# counter.net
KiCad netlist of a schematic drawn in EAGLE
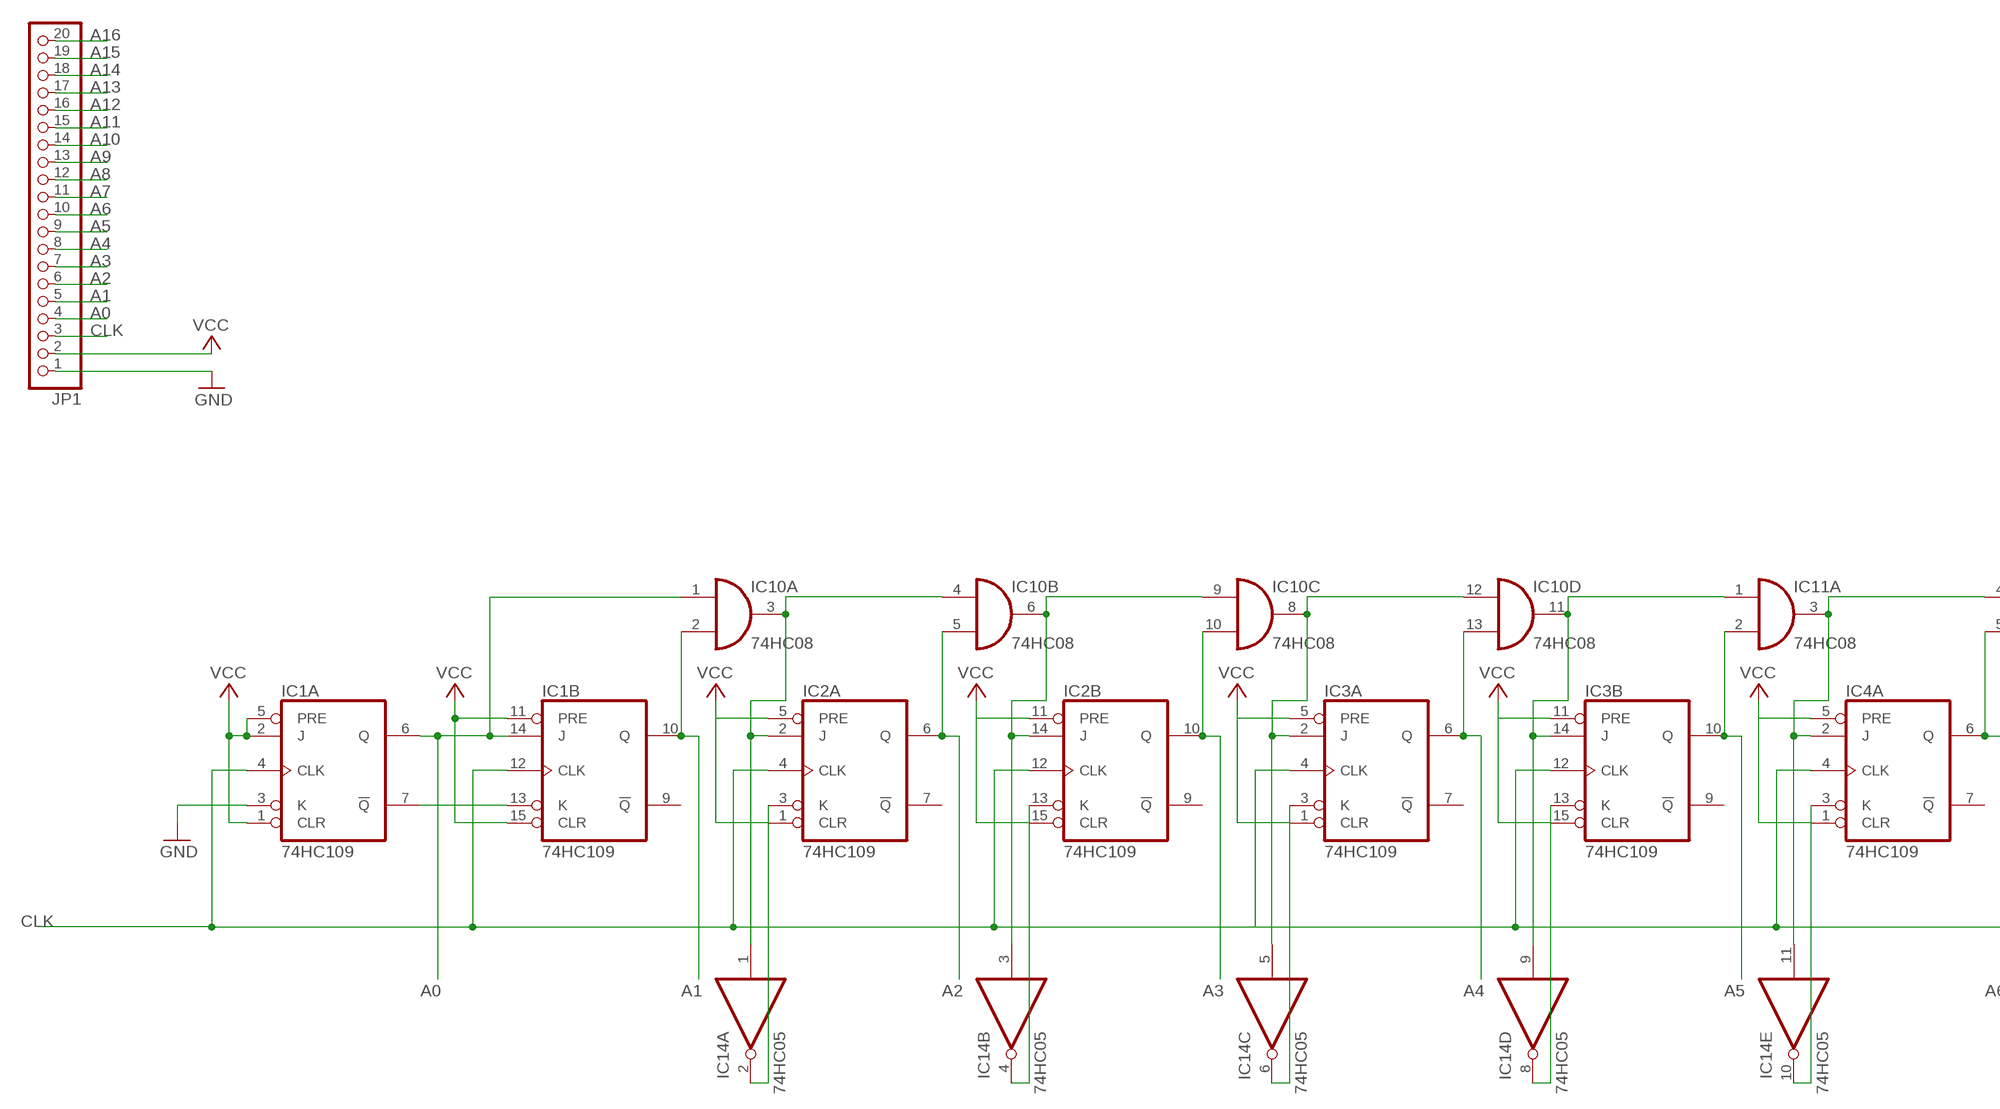
[diagram p0: schematic, sheet 1, part 1 of 2]
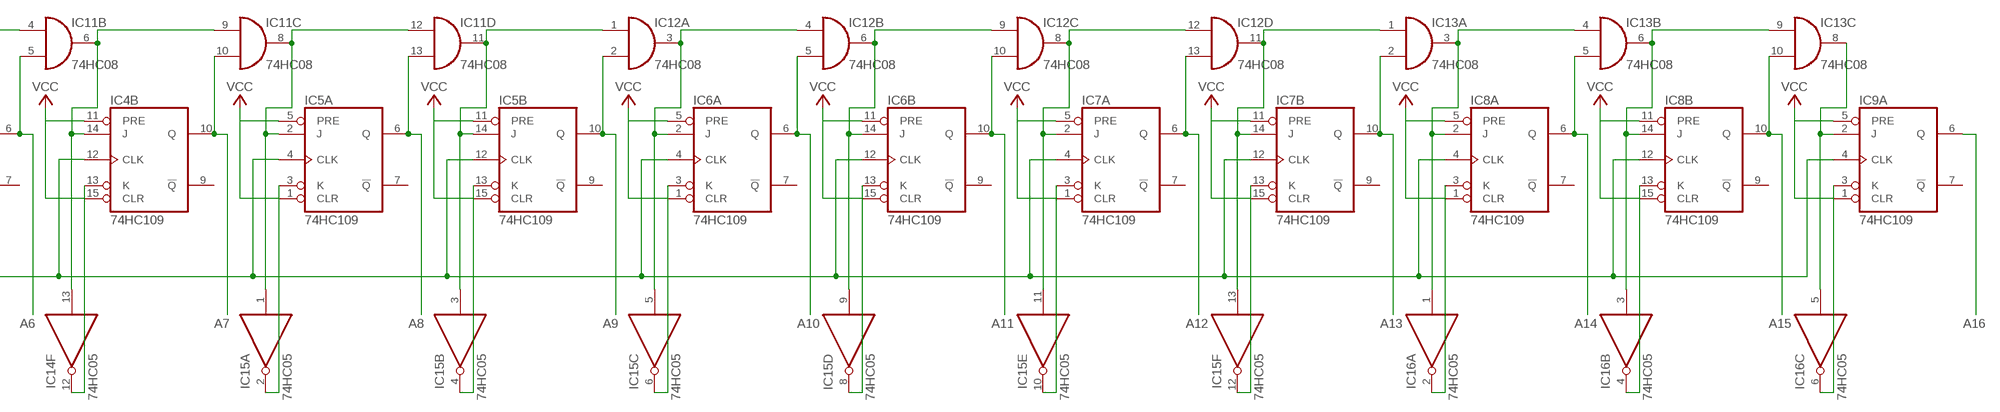
[diagram p1: schematic, sheet 1, part 2 of 2]

(export (version "E")
  (design (tool "Eeschema 10.0.6"))
  (components
    (comp (ref "IC1")
      (value "74HC109")
      (footprint "eagle-import:DIL16")
      (libsource (lib "eagle-import") (part "74109NHC"))
    )
    (comp (ref "IC2")
      (value "74HC109")
      (footprint "eagle-import:DIL16")
      (libsource (lib "eagle-import") (part "74109NHC"))
    )
    (comp (ref "IC3")
      (value "74HC109")
      (footprint "eagle-import:DIL16")
      (libsource (lib "eagle-import") (part "74109NHC"))
    )
    (comp (ref "IC4")
      (value "74HC109")
      (footprint "eagle-import:DIL16")
      (libsource (lib "eagle-import") (part "74109NHC"))
    )
    (comp (ref "IC5")
      (value "74HC109")
      (footprint "eagle-import:DIL16")
      (libsource (lib "eagle-import") (part "74109NHC"))
    )
    (comp (ref "IC6")
      (value "74HC109")
      (footprint "eagle-import:DIL16")
      (libsource (lib "eagle-import") (part "74109NHC"))
    )
    (comp (ref "IC7")
      (value "74HC109")
      (footprint "eagle-import:DIL16")
      (libsource (lib "eagle-import") (part "74109NHC"))
    )
    (comp (ref "IC8")
      (value "74HC109")
      (footprint "eagle-import:DIL16")
      (libsource (lib "eagle-import") (part "74109NHC"))
    )
    (comp (ref "IC9")
      (value "74HC109")
      (footprint "eagle-import:DIL16")
      (libsource (lib "eagle-import") (part "74109NHC"))
    )
    (comp (ref "IC10")
      (value "74HC08")
      (footprint "eagle-import:DIL14")
      (libsource (lib "eagle-import") (part "7408NAC"))
    )
    (comp (ref "IC11")
      (value "74HC08")
      (footprint "eagle-import:DIL14")
      (libsource (lib "eagle-import") (part "7408NAC"))
    )
    (comp (ref "IC12")
      (value "74HC08")
      (footprint "eagle-import:DIL14")
      (libsource (lib "eagle-import") (part "7408NAC"))
    )
    (comp (ref "IC13")
      (value "74HC08")
      (footprint "eagle-import:DIL14")
      (libsource (lib "eagle-import") (part "7408NAC"))
    )
    (comp (ref "IC14")
      (value "74HC05")
      (footprint "eagle-import:DIL14")
      (libsource (lib "eagle-import") (part "7405NALS"))
    )
    (comp (ref "IC15")
      (value "74HC05")
      (footprint "eagle-import:DIL14")
      (libsource (lib "eagle-import") (part "7405NALS"))
    )
    (comp (ref "IC16")
      (value "74HC05")
      (footprint "eagle-import:DIL14")
      (libsource (lib "eagle-import") (part "7405NALS"))
    )
    (comp (ref "JP1")
      (value "PINHD-1X20")
      (footprint "eagle-import:1X20")
      (libsource (lib "eagle-import") (part "PINHD-1X20"))
    )
  )
  (nets
    (net (code "1") (name "/A0") (class "Default")
      (node (ref "IC1") (pin "14") (pinfunction "J_14") (pintype "input"))
      (node (ref "IC1") (pin "6") (pinfunction "Q_6") (pintype "output"))
      (node (ref "IC10") (pin "1") (pinfunction "I0_1") (pintype "input"))
      (node (ref "JP1") (pin "4") (pinfunction "4_4") (pintype "passive"))
    )
    (net (code "2") (name "/A1") (class "Default")
      (node (ref "IC1") (pin "10") (pinfunction "Q_10") (pintype "output"))
      (node (ref "IC10") (pin "2") (pinfunction "I1_2") (pintype "input"))
      (node (ref "JP1") (pin "5") (pinfunction "5_5") (pintype "passive"))
    )
    (net (code "3") (name "/A2") (class "Default")
      (node (ref "IC10") (pin "5") (pinfunction "I1_5") (pintype "input"))
      (node (ref "IC2") (pin "6") (pinfunction "Q_6") (pintype "output"))
      (node (ref "JP1") (pin "6") (pinfunction "6_6") (pintype "passive"))
    )
    (net (code "4") (name "/A3") (class "Default")
      (node (ref "IC10") (pin "10") (pinfunction "I1_10") (pintype "input"))
      (node (ref "IC2") (pin "10") (pinfunction "Q_10") (pintype "output"))
      (node (ref "JP1") (pin "7") (pinfunction "7_7") (pintype "passive"))
    )
    (net (code "5") (name "/A4") (class "Default")
      (node (ref "IC10") (pin "13") (pinfunction "I1_13") (pintype "input"))
      (node (ref "IC3") (pin "6") (pinfunction "Q_6") (pintype "output"))
      (node (ref "JP1") (pin "8") (pinfunction "8_8") (pintype "passive"))
    )
    (net (code "6") (name "/A5") (class "Default")
      (node (ref "IC11") (pin "2") (pinfunction "I1_2") (pintype "input"))
      (node (ref "IC3") (pin "10") (pinfunction "Q_10") (pintype "output"))
      (node (ref "JP1") (pin "9") (pinfunction "9_9") (pintype "passive"))
    )
    (net (code "7") (name "/A6") (class "Default")
      (node (ref "IC11") (pin "5") (pinfunction "I1_5") (pintype "input"))
      (node (ref "IC4") (pin "6") (pinfunction "Q_6") (pintype "output"))
      (node (ref "JP1") (pin "10") (pinfunction "10_10") (pintype "passive"))
    )
    (net (code "8") (name "/A7") (class "Default")
      (node (ref "IC11") (pin "10") (pinfunction "I1_10") (pintype "input"))
      (node (ref "IC4") (pin "10") (pinfunction "Q_10") (pintype "output"))
      (node (ref "JP1") (pin "11") (pinfunction "11_11") (pintype "passive"))
    )
    (net (code "9") (name "/A8") (class "Default")
      (node (ref "IC11") (pin "13") (pinfunction "I1_13") (pintype "input"))
      (node (ref "IC5") (pin "6") (pinfunction "Q_6") (pintype "output"))
      (node (ref "JP1") (pin "12") (pinfunction "12_12") (pintype "passive"))
    )
    (net (code "10") (name "/A9") (class "Default")
      (node (ref "IC12") (pin "2") (pinfunction "I1_2") (pintype "input"))
      (node (ref "IC5") (pin "10") (pinfunction "Q_10") (pintype "output"))
      (node (ref "JP1") (pin "13") (pinfunction "13_13") (pintype "passive"))
    )
    (net (code "11") (name "/A10") (class "Default")
      (node (ref "IC12") (pin "5") (pinfunction "I1_5") (pintype "input"))
      (node (ref "IC6") (pin "6") (pinfunction "Q_6") (pintype "output"))
      (node (ref "JP1") (pin "14") (pinfunction "14_14") (pintype "passive"))
    )
    (net (code "12") (name "/A11") (class "Default")
      (node (ref "IC12") (pin "10") (pinfunction "I1_10") (pintype "input"))
      (node (ref "IC6") (pin "10") (pinfunction "Q_10") (pintype "output"))
      (node (ref "JP1") (pin "15") (pinfunction "15_15") (pintype "passive"))
    )
    (net (code "13") (name "/A12") (class "Default")
      (node (ref "IC12") (pin "13") (pinfunction "I1_13") (pintype "input"))
      (node (ref "IC7") (pin "6") (pinfunction "Q_6") (pintype "output"))
      (node (ref "JP1") (pin "16") (pinfunction "16_16") (pintype "passive"))
    )
    (net (code "14") (name "/A13") (class "Default")
      (node (ref "IC13") (pin "2") (pinfunction "I1_2") (pintype "input"))
      (node (ref "IC7") (pin "10") (pinfunction "Q_10") (pintype "output"))
      (node (ref "JP1") (pin "17") (pinfunction "17_17") (pintype "passive"))
    )
    (net (code "15") (name "/A14") (class "Default")
      (node (ref "IC13") (pin "5") (pinfunction "I1_5") (pintype "input"))
      (node (ref "IC8") (pin "6") (pinfunction "Q_6") (pintype "output"))
      (node (ref "JP1") (pin "18") (pinfunction "18_18") (pintype "passive"))
    )
    (net (code "16") (name "/A15") (class "Default")
      (node (ref "IC13") (pin "10") (pinfunction "I1_10") (pintype "input"))
      (node (ref "IC8") (pin "10") (pinfunction "Q_10") (pintype "output"))
      (node (ref "JP1") (pin "19") (pinfunction "19_19") (pintype "passive"))
    )
    (net (code "17") (name "/A16") (class "Default")
      (node (ref "IC9") (pin "6") (pinfunction "Q_6") (pintype "output"))
      (node (ref "JP1") (pin "20") (pinfunction "20_20") (pintype "passive"))
    )
    (net (code "18") (name "/CLK") (class "Default")
      (node (ref "IC1") (pin "12") (pinfunction "CLK_12") (pintype "input"))
      (node (ref "IC1") (pin "4") (pinfunction "CLK_4") (pintype "input"))
      (node (ref "IC2") (pin "12") (pinfunction "CLK_12") (pintype "input"))
      (node (ref "IC2") (pin "4") (pinfunction "CLK_4") (pintype "input"))
      (node (ref "IC3") (pin "12") (pinfunction "CLK_12") (pintype "input"))
      (node (ref "IC3") (pin "4") (pinfunction "CLK_4") (pintype "input"))
      (node (ref "IC4") (pin "12") (pinfunction "CLK_12") (pintype "input"))
      (node (ref "IC4") (pin "4") (pinfunction "CLK_4") (pintype "input"))
      (node (ref "IC5") (pin "12") (pinfunction "CLK_12") (pintype "input"))
      (node (ref "IC5") (pin "4") (pinfunction "CLK_4") (pintype "input"))
      (node (ref "IC6") (pin "12") (pinfunction "CLK_12") (pintype "input"))
      (node (ref "IC6") (pin "4") (pinfunction "CLK_4") (pintype "input"))
      (node (ref "IC7") (pin "12") (pinfunction "CLK_12") (pintype "input"))
      (node (ref "IC7") (pin "4") (pinfunction "CLK_4") (pintype "input"))
      (node (ref "IC8") (pin "12") (pinfunction "CLK_12") (pintype "input"))
      (node (ref "IC8") (pin "4") (pinfunction "CLK_4") (pintype "input"))
      (node (ref "IC9") (pin "4") (pinfunction "CLK_4") (pintype "input"))
      (node (ref "JP1") (pin "3") (pinfunction "3_3") (pintype "passive"))
    )
    (net (code "19") (name "GND") (class "Default")
      (node (ref "IC1") (pin "3") (pinfunction "K_3") (pintype "input"))
      (node (ref "JP1") (pin "1") (pinfunction "1_1") (pintype "passive"))
    )
    (net (code "20") (name "Net-(IC1A-~{Q})") (class "Default")
      (node (ref "IC1") (pin "13") (pinfunction "K_13") (pintype "input"))
      (node (ref "IC1") (pin "7") (pinfunction "~{Q}_7") (pintype "output"))
    )
    (net (code "21") (name "Net-(IC10A-O)") (class "Default")
      (node (ref "IC10") (pin "3") (pinfunction "O_3") (pintype "output"))
      (node (ref "IC10") (pin "4") (pinfunction "I0_4") (pintype "input"))
      (node (ref "IC14") (pin "1") (pinfunction "I_1") (pintype "input"))
      (node (ref "IC2") (pin "2") (pinfunction "J_2") (pintype "input"))
    )
    (net (code "22") (name "Net-(IC10B-O)") (class "Default")
      (node (ref "IC10") (pin "6") (pinfunction "O_6") (pintype "output"))
      (node (ref "IC10") (pin "9") (pinfunction "I0_9") (pintype "input"))
      (node (ref "IC14") (pin "3") (pinfunction "I_3") (pintype "input"))
      (node (ref "IC2") (pin "14") (pinfunction "J_14") (pintype "input"))
    )
    (net (code "23") (name "Net-(IC10C-O)") (class "Default")
      (node (ref "IC10") (pin "12") (pinfunction "I0_12") (pintype "input"))
      (node (ref "IC10") (pin "8") (pinfunction "O_8") (pintype "output"))
      (node (ref "IC14") (pin "5") (pinfunction "I_5") (pintype "input"))
      (node (ref "IC3") (pin "2") (pinfunction "J_2") (pintype "input"))
    )
    (net (code "24") (name "Net-(IC10D-O)") (class "Default")
      (node (ref "IC10") (pin "11") (pinfunction "O_11") (pintype "output"))
      (node (ref "IC11") (pin "1") (pinfunction "I0_1") (pintype "input"))
      (node (ref "IC14") (pin "9") (pinfunction "I_9") (pintype "input"))
      (node (ref "IC3") (pin "14") (pinfunction "J_14") (pintype "input"))
    )
    (net (code "25") (name "Net-(IC11A-O)") (class "Default")
      (node (ref "IC11") (pin "3") (pinfunction "O_3") (pintype "output"))
      (node (ref "IC11") (pin "4") (pinfunction "I0_4") (pintype "input"))
      (node (ref "IC14") (pin "11") (pinfunction "I_11") (pintype "input"))
      (node (ref "IC4") (pin "2") (pinfunction "J_2") (pintype "input"))
    )
    (net (code "26") (name "Net-(IC11B-O)") (class "Default")
      (node (ref "IC11") (pin "6") (pinfunction "O_6") (pintype "output"))
      (node (ref "IC11") (pin "9") (pinfunction "I0_9") (pintype "input"))
      (node (ref "IC14") (pin "13") (pinfunction "I_13") (pintype "input"))
      (node (ref "IC4") (pin "14") (pinfunction "J_14") (pintype "input"))
    )
    (net (code "27") (name "Net-(IC11C-O)") (class "Default")
      (node (ref "IC11") (pin "12") (pinfunction "I0_12") (pintype "input"))
      (node (ref "IC11") (pin "8") (pinfunction "O_8") (pintype "output"))
      (node (ref "IC15") (pin "1") (pinfunction "I_1") (pintype "input"))
      (node (ref "IC5") (pin "2") (pinfunction "J_2") (pintype "input"))
    )
    (net (code "28") (name "Net-(IC11D-O)") (class "Default")
      (node (ref "IC11") (pin "11") (pinfunction "O_11") (pintype "output"))
      (node (ref "IC12") (pin "1") (pinfunction "I0_1") (pintype "input"))
      (node (ref "IC15") (pin "3") (pinfunction "I_3") (pintype "input"))
      (node (ref "IC5") (pin "14") (pinfunction "J_14") (pintype "input"))
    )
    (net (code "29") (name "Net-(IC12A-O)") (class "Default")
      (node (ref "IC12") (pin "3") (pinfunction "O_3") (pintype "output"))
      (node (ref "IC12") (pin "4") (pinfunction "I0_4") (pintype "input"))
      (node (ref "IC15") (pin "5") (pinfunction "I_5") (pintype "input"))
      (node (ref "IC6") (pin "2") (pinfunction "J_2") (pintype "input"))
    )
    (net (code "30") (name "Net-(IC12B-O)") (class "Default")
      (node (ref "IC12") (pin "6") (pinfunction "O_6") (pintype "output"))
      (node (ref "IC12") (pin "9") (pinfunction "I0_9") (pintype "input"))
      (node (ref "IC15") (pin "9") (pinfunction "I_9") (pintype "input"))
      (node (ref "IC6") (pin "14") (pinfunction "J_14") (pintype "input"))
    )
    (net (code "31") (name "Net-(IC12C-O)") (class "Default")
      (node (ref "IC12") (pin "12") (pinfunction "I0_12") (pintype "input"))
      (node (ref "IC12") (pin "8") (pinfunction "O_8") (pintype "output"))
      (node (ref "IC15") (pin "11") (pinfunction "I_11") (pintype "input"))
      (node (ref "IC7") (pin "2") (pinfunction "J_2") (pintype "input"))
    )
    (net (code "32") (name "Net-(IC12D-O)") (class "Default")
      (node (ref "IC12") (pin "11") (pinfunction "O_11") (pintype "output"))
      (node (ref "IC13") (pin "1") (pinfunction "I0_1") (pintype "input"))
      (node (ref "IC15") (pin "13") (pinfunction "I_13") (pintype "input"))
      (node (ref "IC7") (pin "14") (pinfunction "J_14") (pintype "input"))
    )
    (net (code "33") (name "Net-(IC13A-O)") (class "Default")
      (node (ref "IC13") (pin "3") (pinfunction "O_3") (pintype "output"))
      (node (ref "IC13") (pin "4") (pinfunction "I0_4") (pintype "input"))
      (node (ref "IC16") (pin "1") (pinfunction "I_1") (pintype "input"))
      (node (ref "IC8") (pin "2") (pinfunction "J_2") (pintype "input"))
    )
    (net (code "34") (name "Net-(IC13B-O)") (class "Default")
      (node (ref "IC13") (pin "6") (pinfunction "O_6") (pintype "output"))
      (node (ref "IC13") (pin "9") (pinfunction "I0_9") (pintype "input"))
      (node (ref "IC16") (pin "3") (pinfunction "I_3") (pintype "input"))
      (node (ref "IC8") (pin "14") (pinfunction "J_14") (pintype "input"))
    )
    (net (code "35") (name "Net-(IC13C-O)") (class "Default")
      (node (ref "IC13") (pin "8") (pinfunction "O_8") (pintype "output"))
      (node (ref "IC16") (pin "5") (pinfunction "I_5") (pintype "input"))
      (node (ref "IC9") (pin "2") (pinfunction "J_2") (pintype "input"))
    )
    (net (code "36") (name "Net-(IC14A-O)") (class "Default")
      (node (ref "IC14") (pin "2") (pinfunction "O_2") (pintype "open_collector"))
      (node (ref "IC2") (pin "3") (pinfunction "K_3") (pintype "input"))
    )
    (net (code "37") (name "Net-(IC14B-O)") (class "Default")
      (node (ref "IC14") (pin "4") (pinfunction "O_4") (pintype "open_collector"))
      (node (ref "IC2") (pin "13") (pinfunction "K_13") (pintype "input"))
    )
    (net (code "38") (name "Net-(IC14C-O)") (class "Default")
      (node (ref "IC14") (pin "6") (pinfunction "O_6") (pintype "open_collector"))
      (node (ref "IC3") (pin "3") (pinfunction "K_3") (pintype "input"))
    )
    (net (code "39") (name "Net-(IC14D-O)") (class "Default")
      (node (ref "IC14") (pin "8") (pinfunction "O_8") (pintype "open_collector"))
      (node (ref "IC3") (pin "13") (pinfunction "K_13") (pintype "input"))
    )
    (net (code "40") (name "Net-(IC14E-O)") (class "Default")
      (node (ref "IC14") (pin "10") (pinfunction "O_10") (pintype "open_collector"))
      (node (ref "IC4") (pin "3") (pinfunction "K_3") (pintype "input"))
    )
    (net (code "41") (name "Net-(IC14F-O)") (class "Default")
      (node (ref "IC14") (pin "12") (pinfunction "O_12") (pintype "open_collector"))
      (node (ref "IC4") (pin "13") (pinfunction "K_13") (pintype "input"))
    )
    (net (code "42") (name "Net-(IC15A-O)") (class "Default")
      (node (ref "IC15") (pin "2") (pinfunction "O_2") (pintype "open_collector"))
      (node (ref "IC5") (pin "3") (pinfunction "K_3") (pintype "input"))
    )
    (net (code "43") (name "Net-(IC15B-O)") (class "Default")
      (node (ref "IC15") (pin "4") (pinfunction "O_4") (pintype "open_collector"))
      (node (ref "IC5") (pin "13") (pinfunction "K_13") (pintype "input"))
    )
    (net (code "44") (name "Net-(IC15C-O)") (class "Default")
      (node (ref "IC15") (pin "6") (pinfunction "O_6") (pintype "open_collector"))
      (node (ref "IC6") (pin "3") (pinfunction "K_3") (pintype "input"))
    )
    (net (code "45") (name "Net-(IC15D-O)") (class "Default")
      (node (ref "IC15") (pin "8") (pinfunction "O_8") (pintype "open_collector"))
      (node (ref "IC6") (pin "13") (pinfunction "K_13") (pintype "input"))
    )
    (net (code "46") (name "Net-(IC15E-O)") (class "Default")
      (node (ref "IC15") (pin "10") (pinfunction "O_10") (pintype "open_collector"))
      (node (ref "IC7") (pin "3") (pinfunction "K_3") (pintype "input"))
    )
    (net (code "47") (name "Net-(IC15F-O)") (class "Default")
      (node (ref "IC15") (pin "12") (pinfunction "O_12") (pintype "open_collector"))
      (node (ref "IC7") (pin "13") (pinfunction "K_13") (pintype "input"))
    )
    (net (code "48") (name "Net-(IC16A-O)") (class "Default")
      (node (ref "IC16") (pin "2") (pinfunction "O_2") (pintype "open_collector"))
      (node (ref "IC8") (pin "3") (pinfunction "K_3") (pintype "input"))
    )
    (net (code "49") (name "Net-(IC16B-O)") (class "Default")
      (node (ref "IC16") (pin "4") (pinfunction "O_4") (pintype "open_collector"))
      (node (ref "IC8") (pin "13") (pinfunction "K_13") (pintype "input"))
    )
    (net (code "50") (name "Net-(IC16C-O)") (class "Default")
      (node (ref "IC16") (pin "6") (pinfunction "O_6") (pintype "open_collector"))
      (node (ref "IC9") (pin "3") (pinfunction "K_3") (pintype "input"))
    )
    (net (code "51") (name "VCC") (class "Default")
      (node (ref "IC1") (pin "1") (pinfunction "CLR_1") (pintype "input"))
      (node (ref "IC1") (pin "11") (pinfunction "PRE_11") (pintype "input"))
      (node (ref "IC1") (pin "15") (pinfunction "CLR_15") (pintype "input"))
      (node (ref "IC1") (pin "2") (pinfunction "J_2") (pintype "input"))
      (node (ref "IC1") (pin "5") (pinfunction "PRE_5") (pintype "input"))
      (node (ref "IC2") (pin "1") (pinfunction "CLR_1") (pintype "input"))
      (node (ref "IC2") (pin "11") (pinfunction "PRE_11") (pintype "input"))
      (node (ref "IC2") (pin "15") (pinfunction "CLR_15") (pintype "input"))
      (node (ref "IC2") (pin "5") (pinfunction "PRE_5") (pintype "input"))
      (node (ref "IC3") (pin "1") (pinfunction "CLR_1") (pintype "input"))
      (node (ref "IC3") (pin "11") (pinfunction "PRE_11") (pintype "input"))
      (node (ref "IC3") (pin "15") (pinfunction "CLR_15") (pintype "input"))
      (node (ref "IC3") (pin "5") (pinfunction "PRE_5") (pintype "input"))
      (node (ref "IC4") (pin "1") (pinfunction "CLR_1") (pintype "input"))
      (node (ref "IC4") (pin "11") (pinfunction "PRE_11") (pintype "input"))
      (node (ref "IC4") (pin "15") (pinfunction "CLR_15") (pintype "input"))
      (node (ref "IC4") (pin "5") (pinfunction "PRE_5") (pintype "input"))
      (node (ref "IC5") (pin "1") (pinfunction "CLR_1") (pintype "input"))
      (node (ref "IC5") (pin "11") (pinfunction "PRE_11") (pintype "input"))
      (node (ref "IC5") (pin "15") (pinfunction "CLR_15") (pintype "input"))
      (node (ref "IC5") (pin "5") (pinfunction "PRE_5") (pintype "input"))
      (node (ref "IC6") (pin "1") (pinfunction "CLR_1") (pintype "input"))
      (node (ref "IC6") (pin "11") (pinfunction "PRE_11") (pintype "input"))
      (node (ref "IC6") (pin "15") (pinfunction "CLR_15") (pintype "input"))
      (node (ref "IC6") (pin "5") (pinfunction "PRE_5") (pintype "input"))
      (node (ref "IC7") (pin "1") (pinfunction "CLR_1") (pintype "input"))
      (node (ref "IC7") (pin "11") (pinfunction "PRE_11") (pintype "input"))
      (node (ref "IC7") (pin "15") (pinfunction "CLR_15") (pintype "input"))
      (node (ref "IC7") (pin "5") (pinfunction "PRE_5") (pintype "input"))
      (node (ref "IC8") (pin "1") (pinfunction "CLR_1") (pintype "input"))
      (node (ref "IC8") (pin "11") (pinfunction "PRE_11") (pintype "input"))
      (node (ref "IC8") (pin "15") (pinfunction "CLR_15") (pintype "input"))
      (node (ref "IC8") (pin "5") (pinfunction "PRE_5") (pintype "input"))
      (node (ref "IC9") (pin "1") (pinfunction "CLR_1") (pintype "input"))
      (node (ref "IC9") (pin "5") (pinfunction "PRE_5") (pintype "input"))
      (node (ref "JP1") (pin "2") (pinfunction "2_2") (pintype "passive"))
    )
    (net (code "52") (name "unconnected-(IC1B-~{Q}-Pad9)") (class "Default")
      (node (ref "IC1") (pin "9") (pinfunction "~{Q}_9") (pintype "output"))
    )
    (net (code "53") (name "unconnected-(IC2A-~{Q}-Pad7)") (class "Default")
      (node (ref "IC2") (pin "7") (pinfunction "~{Q}_7") (pintype "output"))
    )
    (net (code "54") (name "unconnected-(IC2B-~{Q}-Pad9)") (class "Default")
      (node (ref "IC2") (pin "9") (pinfunction "~{Q}_9") (pintype "output"))
    )
    (net (code "55") (name "unconnected-(IC3A-~{Q}-Pad7)") (class "Default")
      (node (ref "IC3") (pin "7") (pinfunction "~{Q}_7") (pintype "output"))
    )
    (net (code "56") (name "unconnected-(IC3B-~{Q}-Pad9)") (class "Default")
      (node (ref "IC3") (pin "9") (pinfunction "~{Q}_9") (pintype "output"))
    )
    (net (code "57") (name "unconnected-(IC4A-~{Q}-Pad7)") (class "Default")
      (node (ref "IC4") (pin "7") (pinfunction "~{Q}_7") (pintype "output"))
    )
    (net (code "58") (name "unconnected-(IC4B-~{Q}-Pad9)") (class "Default")
      (node (ref "IC4") (pin "9") (pinfunction "~{Q}_9") (pintype "output"))
    )
    (net (code "59") (name "unconnected-(IC5A-~{Q}-Pad7)") (class "Default")
      (node (ref "IC5") (pin "7") (pinfunction "~{Q}_7") (pintype "output"))
    )
    (net (code "60") (name "unconnected-(IC5B-~{Q}-Pad9)") (class "Default")
      (node (ref "IC5") (pin "9") (pinfunction "~{Q}_9") (pintype "output"))
    )
    (net (code "61") (name "unconnected-(IC6A-~{Q}-Pad7)") (class "Default")
      (node (ref "IC6") (pin "7") (pinfunction "~{Q}_7") (pintype "output"))
    )
    (net (code "62") (name "unconnected-(IC6B-~{Q}-Pad9)") (class "Default")
      (node (ref "IC6") (pin "9") (pinfunction "~{Q}_9") (pintype "output"))
    )
    (net (code "63") (name "unconnected-(IC7A-~{Q}-Pad7)") (class "Default")
      (node (ref "IC7") (pin "7") (pinfunction "~{Q}_7") (pintype "output"))
    )
    (net (code "64") (name "unconnected-(IC7B-~{Q}-Pad9)") (class "Default")
      (node (ref "IC7") (pin "9") (pinfunction "~{Q}_9") (pintype "output"))
    )
    (net (code "65") (name "unconnected-(IC8A-~{Q}-Pad7)") (class "Default")
      (node (ref "IC8") (pin "7") (pinfunction "~{Q}_7") (pintype "output"))
    )
    (net (code "66") (name "unconnected-(IC8B-~{Q}-Pad9)") (class "Default")
      (node (ref "IC8") (pin "9") (pinfunction "~{Q}_9") (pintype "output"))
    )
    (net (code "67") (name "unconnected-(IC9A-~{Q}-Pad7)") (class "Default")
      (node (ref "IC9") (pin "7") (pinfunction "~{Q}_7") (pintype "output"))
    )
  )
)
